# ESP32_Sheet.net
KiCad netlist of a schematic drawn in Altium Designer
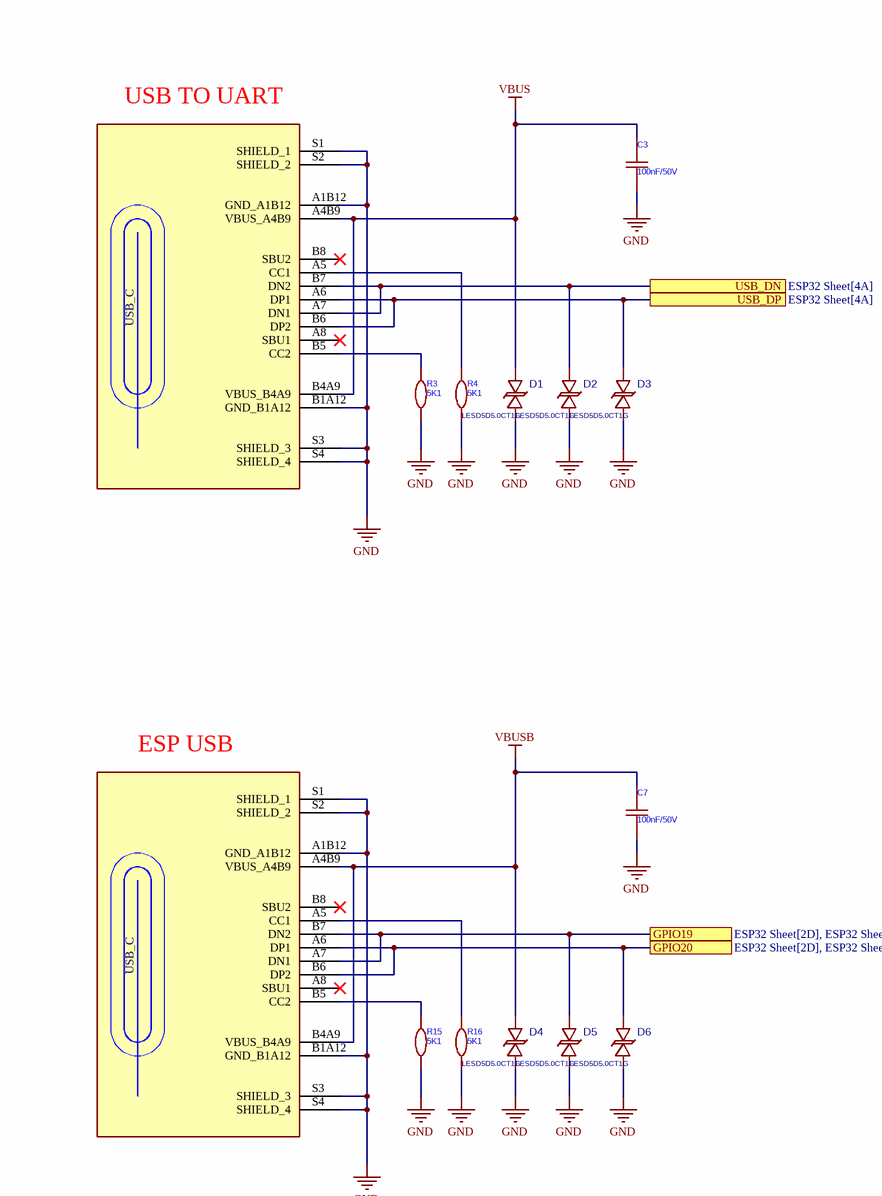
[diagram p0: ESP32 Sheet.SchDoc, top left]
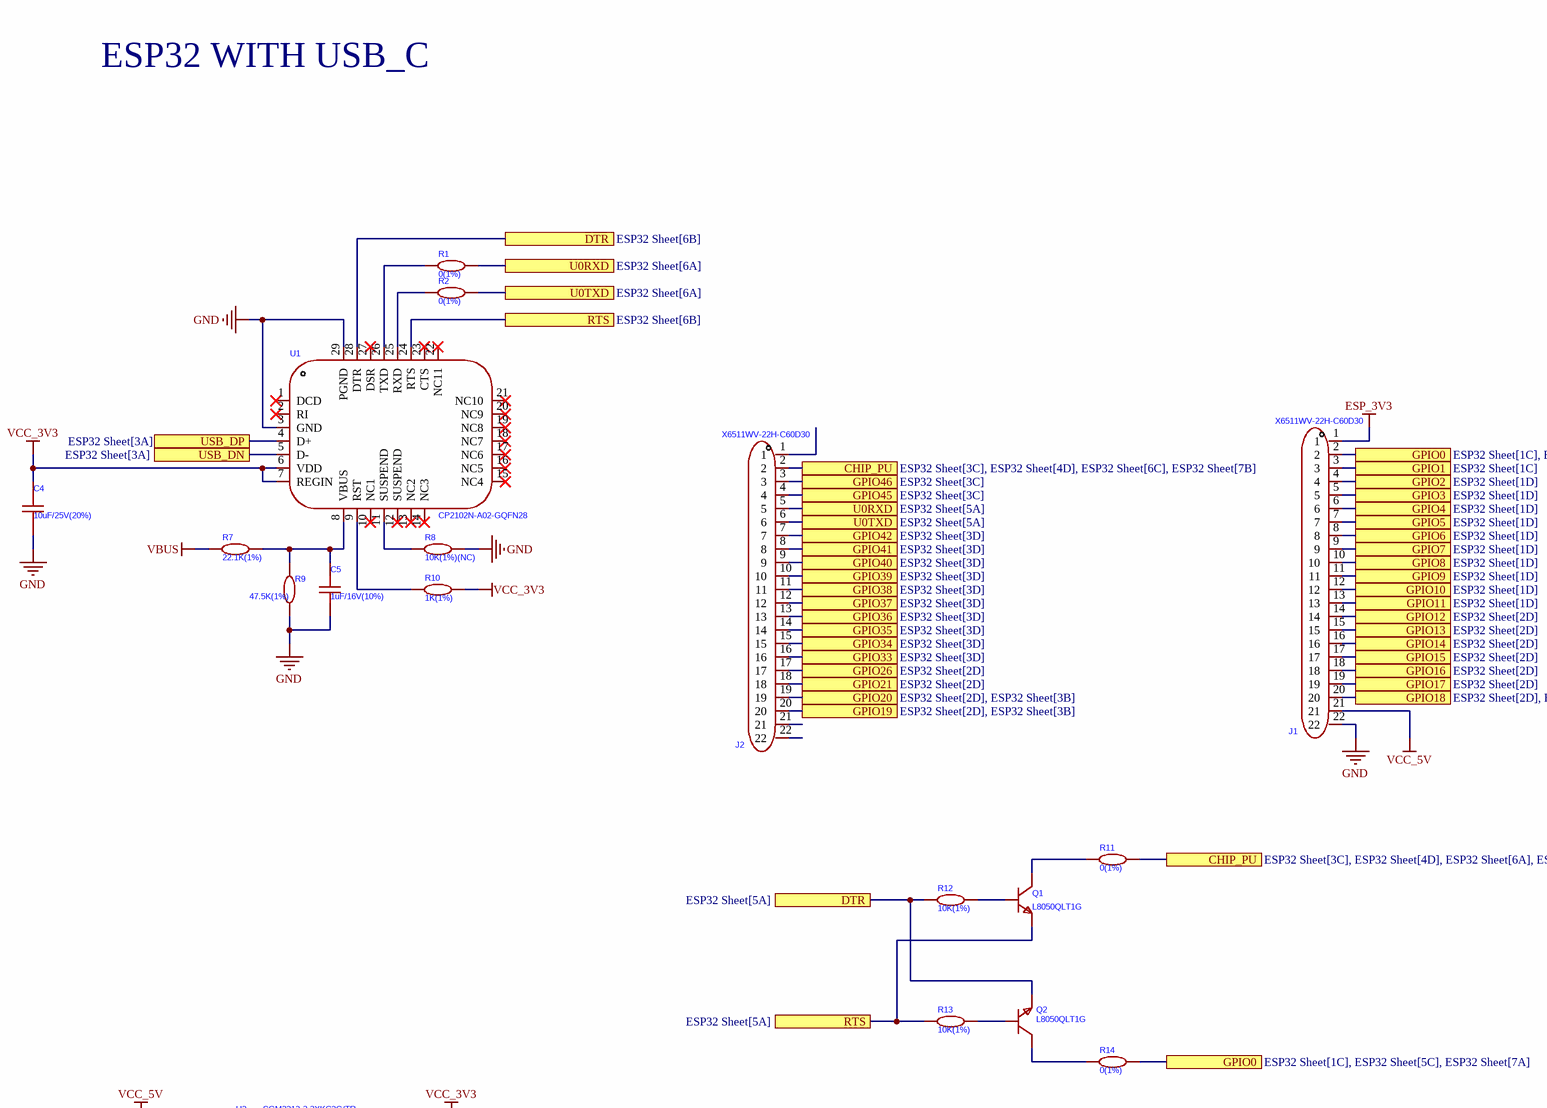
[diagram p1: ESP32 Sheet.SchDoc, top right]
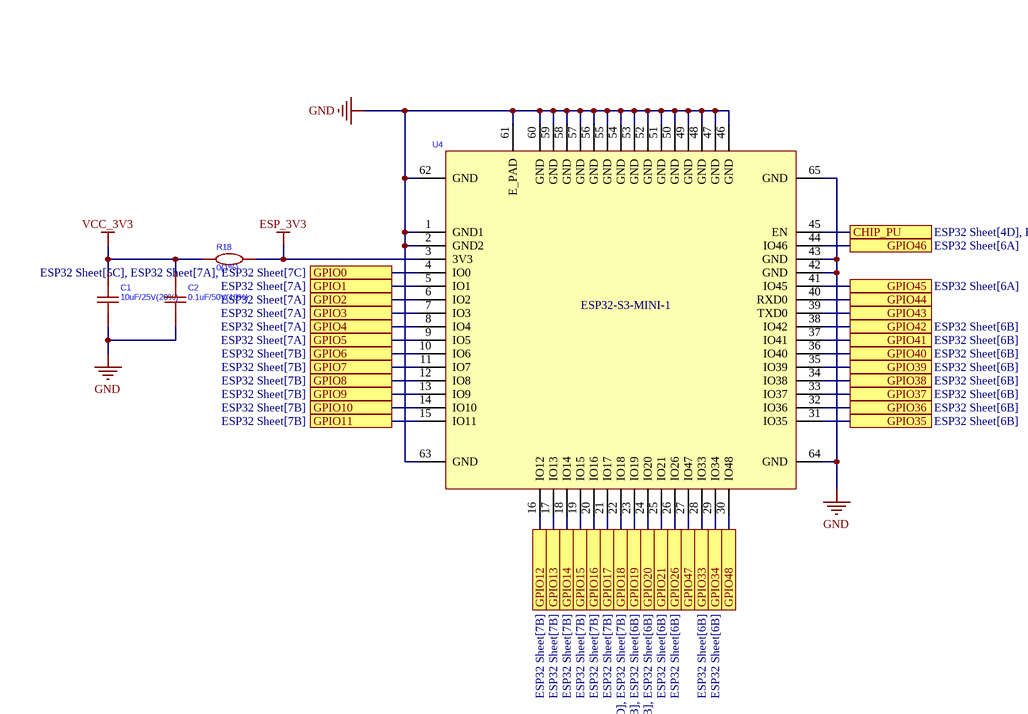
[diagram p2: ESP32 Sheet.SchDoc, bottom left]
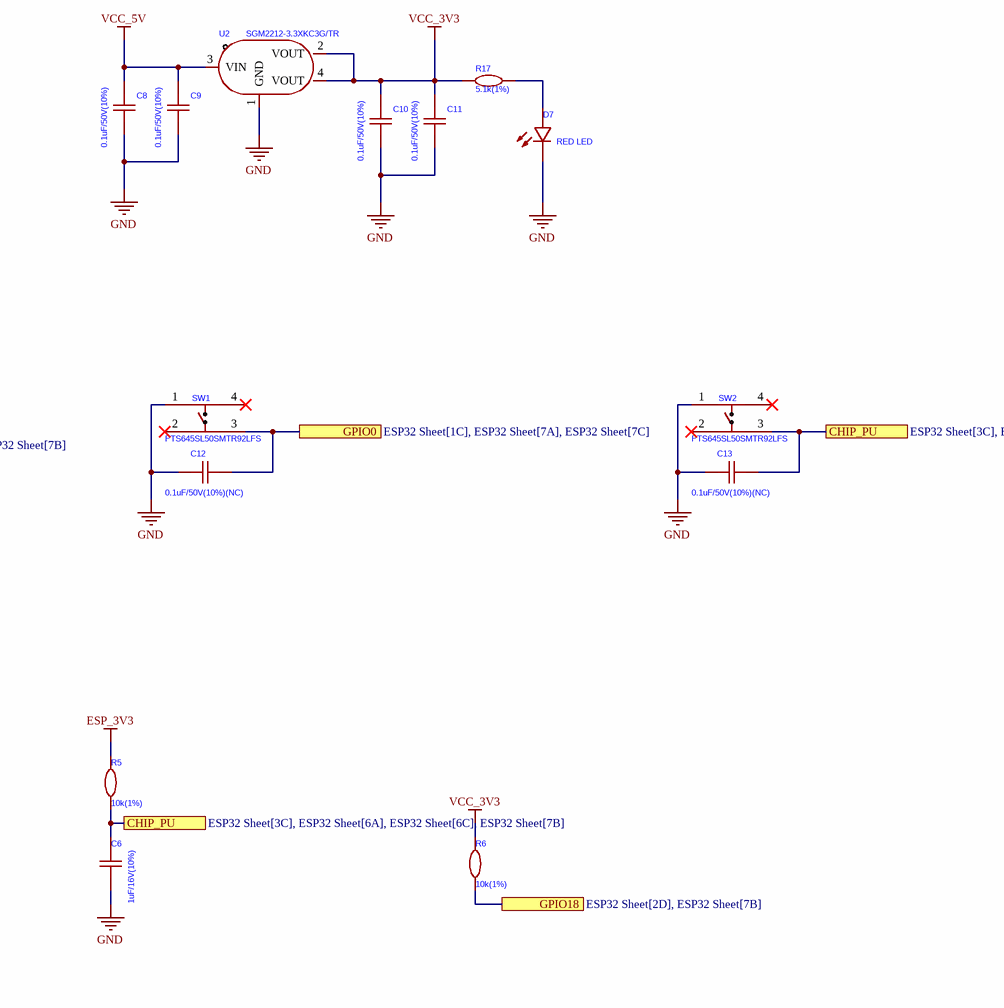
[diagram p3: ESP32 Sheet.SchDoc, bottom right]

(export (version "E")
  (design (tool "Eeschema 10.0.6"))
  (components
    (comp (ref "C1")
      (value "10uF/25V(20%)")
      (footprint "C0402")
      (fields
        (field (name "MANUFACTURER") "SAMSUNG(三星)")
        (field (name "MANUFACTURER PART") "CL05B104KB54PNC")
        (field (name "TOLERANCE") "±10%")
      )
      (libsource (lib "altium-import") (part "root_1_CL05B104KB54PNC_"))
    )
    (comp (ref "C2")
      (value "0.1uF/50V(10%)")
      (footprint "C0402")
      (fields
        (field (name "MANUFACTURER") "SAMSUNG(三星)")
        (field (name "MANUFACTURER PART") "CL05B104KB54PNC")
        (field (name "TOLERANCE") "±10%")
      )
      (libsource (lib "altium-import") (part "root_1_CL05B104KB54PNC_"))
    )
    (comp (ref "C3")
      (value "100nF/50V")
      (footprint "C0402")
      (fields
        (field (name "MANUFACTURER") "SAMSUNG(三星)")
        (field (name "MANUFACTURER PART") "CL05B104KB54PNC")
        (field (name "TOLERANCE") "±10%")
      )
      (libsource (lib "altium-import") (part "root_3_CL05B104KB54PNC_"))
    )
    (comp (ref "C4")
      (value "10uF/25V(20%)")
      (footprint "C0402")
      (fields
        (field (name "MANUFACTURER") "SAMSUNG(三星)")
        (field (name "MANUFACTURER PART") "CL05B104KB54PNC")
        (field (name "TOLERANCE") "±10%")
      )
      (libsource (lib "altium-import") (part "root_3_CL05B104KB54PNC_"))
    )
    (comp (ref "C5")
      (value "1uF/16V(10%)")
      (footprint "C0402")
      (fields
        (field (name "MANUFACTURER") "SAMSUNG(三星)")
        (field (name "MANUFACTURER PART") "CL05B104KB54PNC")
        (field (name "TOLERANCE") "±10%")
      )
      (libsource (lib "altium-import") (part "root_3_CL05B104KB54PNC_"))
    )
    (comp (ref "C6")
      (value "1uF/16V(10%)")
      (footprint "C0402")
      (fields
        (field (name "MANUFACTURER") "SAMSUNG(三星)")
        (field (name "MANUFACTURER PART") "CL05B104KB54PNC")
        (field (name "TOLERANCE") "±10%")
      )
      (libsource (lib "altium-import") (part "root_3_CL05B104KB54PNC_"))
    )
    (comp (ref "C7")
      (value "100nF/50V")
      (footprint "C0402")
      (fields
        (field (name "MANUFACTURER") "SAMSUNG(三星)")
        (field (name "MANUFACTURER PART") "CL05B104KB54PNC")
        (field (name "TOLERANCE") "±10%")
      )
      (libsource (lib "altium-import") (part "root_3_CL05B104KB54PNC_"))
    )
    (comp (ref "C8")
      (value "0.1uF/50V(10%)")
      (footprint "C0402")
      (fields
        (field (name "MANUFACTURER") "SAMSUNG(三星)")
        (field (name "MANUFACTURER PART") "CL05B104KB54PNC")
        (field (name "TOLERANCE") "±10%")
      )
      (libsource (lib "altium-import") (part "root_1_CL05B104KB54PNC_"))
    )
    (comp (ref "C9")
      (value "0.1uF/50V(10%)")
      (footprint "C0402")
      (fields
        (field (name "MANUFACTURER") "SAMSUNG(三星)")
        (field (name "MANUFACTURER PART") "CL05B104KB54PNC")
        (field (name "TOLERANCE") "±10%")
      )
      (libsource (lib "altium-import") (part "root_1_CL05B104KB54PNC_"))
    )
    (comp (ref "C10")
      (value "0.1uF/50V(10%)")
      (footprint "C0402")
      (fields
        (field (name "MANUFACTURER") "SAMSUNG(三星)")
        (field (name "MANUFACTURER PART") "CL05B104KB54PNC")
        (field (name "TOLERANCE") "±10%")
      )
      (libsource (lib "altium-import") (part "root_1_CL05B104KB54PNC_"))
    )
    (comp (ref "C11")
      (value "0.1uF/50V(10%)")
      (footprint "C0402")
      (fields
        (field (name "MANUFACTURER") "SAMSUNG(三星)")
        (field (name "MANUFACTURER PART") "CL05B104KB54PNC")
        (field (name "TOLERANCE") "±10%")
      )
      (libsource (lib "altium-import") (part "root_1_CL05B104KB54PNC_"))
    )
    (comp (ref "C12")
      (value "0.1uF/50V(10%)(NC)")
      (footprint "C0402")
      (fields
        (field (name "MANUFACTURER") "SAMSUNG(三星)")
        (field (name "MANUFACTURER PART") "CL05B104KB54PNC")
        (field (name "TOLERANCE") "±10%")
      )
      (libsource (lib "altium-import") (part "root_0_CL05B104KB54PNC_"))
    )
    (comp (ref "C13")
      (value "0.1uF/50V(10%)(NC)")
      (footprint "C0402")
      (fields
        (field (name "MANUFACTURER") "SAMSUNG(三星)")
        (field (name "MANUFACTURER PART") "CL05B104KB54PNC")
        (field (name "TOLERANCE") "±10%")
      )
      (libsource (lib "altium-import") (part "root_0_CL05B104KB54PNC_"))
    )
    (comp (ref "D1")
      (value "LESD5D5.0CT1G")
      (footprint "SOD-523_L1.2-W0.8-LS1.6-BI")
      (fields (field (name "MANUFACTURER") "UMW(友台半导体)") (field (name "CONTRIBUTOR") "lcsc"))
      (libsource (lib "altium-import") (part "root_1_LESD5D5.0CT1G_C5199850_"))
    )
    (comp (ref "D2")
      (value "LESD5D5.0CT1G")
      (footprint "SOD-523_L1.2-W0.8-LS1.6-BI")
      (fields (field (name "MANUFACTURER") "UMW(友台半导体)") (field (name "CONTRIBUTOR") "lcsc"))
      (libsource (lib "altium-import") (part "root_1_LESD5D5.0CT1G_C5199850_"))
    )
    (comp (ref "D3")
      (value "LESD5D5.0CT1G")
      (footprint "SOD-523_L1.2-W0.8-LS1.6-BI")
      (fields (field (name "MANUFACTURER") "UMW(友台半导体)") (field (name "CONTRIBUTOR") "lcsc"))
      (libsource (lib "altium-import") (part "root_1_LESD5D5.0CT1G_C5199850_"))
    )
    (comp (ref "D4")
      (value "LESD5D5.0CT1G")
      (footprint "SOD-523_L1.2-W0.8-LS1.6-BI")
      (fields (field (name "MANUFACTURER") "UMW(友台半导体)") (field (name "CONTRIBUTOR") "lcsc"))
      (libsource (lib "altium-import") (part "root_1_LESD5D5.0CT1G_C5199850_"))
    )
    (comp (ref "D5")
      (value "LESD5D5.0CT1G")
      (footprint "SOD-523_L1.2-W0.8-LS1.6-BI")
      (fields (field (name "MANUFACTURER") "UMW(友台半导体)") (field (name "CONTRIBUTOR") "lcsc"))
      (libsource (lib "altium-import") (part "root_1_LESD5D5.0CT1G_C5199850_"))
    )
    (comp (ref "D6")
      (value "LESD5D5.0CT1G")
      (footprint "SOD-523_L1.2-W0.8-LS1.6-BI")
      (fields (field (name "MANUFACTURER") "UMW(友台半导体)") (field (name "CONTRIBUTOR") "lcsc"))
      (libsource (lib "altium-import") (part "root_1_LESD5D5.0CT1G_C5199850_"))
    )
    (comp (ref "D7")
      (value "RED LED")
      (footprint "LED0402-R-RD")
      (fields
        (field (name "MANUFACTURER") "EVERLIGHT(亿光)")
        (field (name "MANUFACTURER PART") "16-213SDRC/S530-A3/TR8")
      )
      (libsource (lib "altium-import") (part "root_1_16-213SDRC/S530-A3/TR8_"))
    )
    (comp (ref "J1")
      (value "X6511WV-22H-C60D30")
      (footprint "HDR-TH_22P-P2.54-V-M")
      (fields (field (name "MANUFACTURER") "XKB Connection(中国星坤)"))
      (libsource (lib "altium-import") (part "root_0_mirrored_X6511WV-22H-C60D30_"))
    )
    (comp (ref "J2")
      (value "X6511WV-22H-C60D30")
      (footprint "HDR-TH_22P-P2.54-V-M")
      (fields (field (name "MANUFACTURER") "XKB Connection(中国星坤)"))
      (libsource (lib "altium-import") (part "root_0_mirrored_X6511WV-22H-C60D30_"))
    )
    (comp (ref "Q1")
      (value "L8050QLT1G")
      (footprint "SOT-23-3_L2.9-W1.3-P1.90-LS2.4-BR")
      (fields (field (name "MANUFACTURER") "LRC(乐山无线电)"))
      (libsource (lib "altium-import") (part "root_0_L8050QLT1G_"))
    )
    (comp (ref "Q2")
      (value "L8050QLT1G")
      (footprint "SOT-23-3_L2.9-W1.3-P1.90-LS2.4-BR")
      (fields (field (name "MANUFACTURER") "LRC(乐山无线电)"))
      (libsource (lib "altium-import") (part "root_2_mirrored_L8050QLT1G_"))
    )
    (comp (ref "R1")
      (value "0(1%)")
      (footprint "R0402")
      (fields
        (field (name "MANUFACTURER") "YAGEO(国巨)")
        (field (name "MANUFACTURER PART") "AC0402FR-0710KL")
        (field (name "TOLERANCE") "±1%")
      )
      (libsource (lib "altium-import") (part "root_2_AC0402FR-0710KL_"))
    )
    (comp (ref "R2")
      (value "0(1%)")
      (footprint "R0402")
      (fields
        (field (name "MANUFACTURER") "YAGEO(国巨)")
        (field (name "MANUFACTURER PART") "AC0402FR-0710KL")
        (field (name "TOLERANCE") "±1%")
      )
      (libsource (lib "altium-import") (part "root_2_AC0402FR-0710KL_"))
    )
    (comp (ref "R3")
      (value "5K1")
      (footprint "R0402")
      (fields
        (field (name "MANUFACTURER") "YAGEO(国巨)")
        (field (name "MANUFACTURER PART") "AC0402FR-0710KL")
        (field (name "TOLERANCE") "±1%")
      )
      (libsource (lib "altium-import") (part "root_1_AC0402FR-0710KL_"))
    )
    (comp (ref "R4")
      (value "5K1")
      (footprint "R0402")
      (fields
        (field (name "MANUFACTURER") "YAGEO(国巨)")
        (field (name "MANUFACTURER PART") "AC0402FR-0710KL")
        (field (name "TOLERANCE") "±1%")
      )
      (libsource (lib "altium-import") (part "root_1_AC0402FR-0710KL_"))
    )
    (comp (ref "R5")
      (value "10k(1%)")
      (footprint "R0402")
      (fields
        (field (name "MANUFACTURER") "YAGEO(国巨)")
        (field (name "MANUFACTURER PART") "AC0402FR-0710KL")
        (field (name "TOLERANCE") "±1%")
      )
      (libsource (lib "altium-import") (part "root_1_AC0402FR-0710KL_"))
    )
    (comp (ref "R6")
      (value "10k(1%)")
      (footprint "R0402")
      (fields
        (field (name "MANUFACTURER") "YAGEO(国巨)")
        (field (name "MANUFACTURER PART") "AC0402FR-0710KL")
        (field (name "TOLERANCE") "±1%")
      )
      (libsource (lib "altium-import") (part "root_1_AC0402FR-0710KL_"))
    )
    (comp (ref "R7")
      (value "22.1K(1%)")
      (footprint "R0402")
      (fields
        (field (name "MANUFACTURER") "YAGEO(国巨)")
        (field (name "MANUFACTURER PART") "AC0402FR-0710KL")
        (field (name "TOLERANCE") "±1%")
      )
      (libsource (lib "altium-import") (part "root_2_AC0402FR-0710KL_"))
    )
    (comp (ref "R8")
      (value "10K(1%)(NC)")
      (footprint "R0402")
      (fields
        (field (name "MANUFACTURER") "YAGEO(国巨)")
        (field (name "MANUFACTURER PART") "AC0402FR-0710KL")
        (field (name "TOLERANCE") "±1%")
      )
      (libsource (lib "altium-import") (part "root_2_AC0402FR-0710KL_"))
    )
    (comp (ref "R9")
      (value "47.5K(1%)")
      (footprint "R0402")
      (fields
        (field (name "MANUFACTURER") "YAGEO(国巨)")
        (field (name "MANUFACTURER PART") "AC0402FR-0710KL")
        (field (name "TOLERANCE") "±1%")
      )
      (libsource (lib "altium-import") (part "root_1_AC0402FR-0710KL_"))
    )
    (comp (ref "R10")
      (value "1K(1%)")
      (footprint "R0402")
      (fields
        (field (name "MANUFACTURER") "YAGEO(国巨)")
        (field (name "MANUFACTURER PART") "AC0402FR-0710KL")
        (field (name "TOLERANCE") "±1%")
      )
      (libsource (lib "altium-import") (part "root_2_AC0402FR-0710KL_"))
    )
    (comp (ref "R11")
      (value "0(1%)")
      (footprint "R0402")
      (fields
        (field (name "MANUFACTURER") "YAGEO(国巨)")
        (field (name "MANUFACTURER PART") "AC0402FR-0710KL")
        (field (name "TOLERANCE") "±1%")
      )
      (libsource (lib "altium-import") (part "root_2_AC0402FR-0710KL_"))
    )
    (comp (ref "R12")
      (value "10K(1%)")
      (footprint "R0402")
      (fields
        (field (name "MANUFACTURER") "YAGEO(国巨)")
        (field (name "MANUFACTURER PART") "AC0402FR-0710KL")
        (field (name "TOLERANCE") "±1%")
      )
      (libsource (lib "altium-import") (part "root_2_AC0402FR-0710KL_"))
    )
    (comp (ref "R13")
      (value "10K(1%)")
      (footprint "R0402")
      (fields
        (field (name "MANUFACTURER") "YAGEO(国巨)")
        (field (name "MANUFACTURER PART") "AC0402FR-0710KL")
        (field (name "TOLERANCE") "±1%")
      )
      (libsource (lib "altium-import") (part "root_2_AC0402FR-0710KL_"))
    )
    (comp (ref "R14")
      (value "0(1%)")
      (footprint "R0402")
      (fields
        (field (name "MANUFACTURER") "YAGEO(国巨)")
        (field (name "MANUFACTURER PART") "AC0402FR-0710KL")
        (field (name "TOLERANCE") "±1%")
      )
      (libsource (lib "altium-import") (part "root_2_AC0402FR-0710KL_"))
    )
    (comp (ref "R15")
      (value "5K1")
      (footprint "R0402")
      (fields
        (field (name "MANUFACTURER") "YAGEO(国巨)")
        (field (name "MANUFACTURER PART") "AC0402FR-0710KL")
        (field (name "TOLERANCE") "±1%")
      )
      (libsource (lib "altium-import") (part "root_1_AC0402FR-0710KL_"))
    )
    (comp (ref "R16")
      (value "5K1")
      (footprint "R0402")
      (fields
        (field (name "MANUFACTURER") "YAGEO(国巨)")
        (field (name "MANUFACTURER PART") "AC0402FR-0710KL")
        (field (name "TOLERANCE") "±1%")
      )
      (libsource (lib "altium-import") (part "root_1_AC0402FR-0710KL_"))
    )
    (comp (ref "R17")
      (value "5.1k(1%)")
      (footprint "R0402")
      (fields
        (field (name "MANUFACTURER") "YAGEO(国巨)")
        (field (name "MANUFACTURER PART") "AC0402FR-0710KL")
        (field (name "TOLERANCE") "±1%")
      )
      (libsource (lib "altium-import") (part "root_2_AC0402FR-0710KL_"))
    )
    (comp (ref "R18")
      (value "0(1%)")
      (footprint "R0402")
      (fields
        (field (name "MANUFACTURER") "YAGEO(国巨)")
        (field (name "MANUFACTURER PART") "AC0402FR-0710KL")
        (field (name "TOLERANCE") "±1%")
      )
      (libsource (lib "altium-import") (part "root_2_AC0402FR-0710KL_"))
    )
    (comp (ref "SW1")
      (value "PTS645SL50SMTR92LFS")
      (footprint "KEY-SMD_4P-L6.0-W6.0-P4.50-LS9.0")
      (fields (field (name "MANUFACTURER") "C&K"))
      (libsource (lib "Schlib1") (part "PTS645SL50SMTR92LFS"))
    )
    (comp (ref "SW2")
      (value "PTS645SL50SMTR92LFS")
      (footprint "KEY-SMD_4P-L6.0-W6.0-P4.50-LS9.0")
      (fields (field (name "MANUFACTURER") "C&K"))
      (libsource (lib "Schlib1") (part "PTS645SL50SMTR92LFS"))
    )
    (comp (ref "U1")
      (value "CP2102N-A02-GQFN28")
      (footprint "QFN-28_L5.0-W5.0-P0.50-TL-EP3.3")
      (fields (field (name "MANUFACTURER") "SKYWORKS/SILICON LABS(芯科)"))
      (libsource (lib "Schlib1") (part "CP2102N-A02-GQFN28"))
    )
    (comp (ref "U2")
      (value "SGM2212-3.3XKC3G/TR")
      (footprint "SOT-223-3_L6.5-W3.4-P2.30-LS7.0-BR")
      (fields (field (name "MANUFACTURER") "SGMICRO(圣邦微)"))
      (libsource (lib "Schlib1") (part "SGM2212-3.3XKC3G/TR_C3294699"))
    )
    (comp (ref "U4")
      (value "2.4GHz")
      (footprint "BULETM-SMD_ESP32-S3-MINI-1-N8")
      (fields
        (field (name "MANUFACTURER") "ESPRESSIF(乐鑫)")
        (field (name "MANUFACTURER PART") "ESP32-S3-MINI-1-N8")
      )
      (libsource (lib "Schlib1") (part "ESP32-S3-MINI-1-N8"))
    )
    (comp (ref "USB1")
      (value "2171790001")
      (footprint "USB-C-SMD_2171790001")
      (fields (field (name "MANUFACTURER") "MOLEX"))
      (libsource (lib "Schlib1") (part "2171790001"))
    )
    (comp (ref "USB2")
      (value "2171790001")
      (footprint "USB-C-SMD_2171790001")
      (fields (field (name "MANUFACTURER") "MOLEX"))
      (libsource (lib "Schlib1") (part "2171790001"))
    )
  )
  (nets
    (net (code "1") (name "/CHIP_PU") (class "Default")
      (node (ref "C13") (pin "2") (pinfunction "2_2") (pintype "passive"))
      (node (ref "C6") (pin "1") (pinfunction "1_1") (pintype "passive"))
      (node (ref "J2") (pin "2") (pinfunction "2_2") (pintype "passive"))
      (node (ref "R11") (pin "1") (pinfunction "1_1") (pintype "passive"))
      (node (ref "R5") (pin "1") (pinfunction "1_1") (pintype "passive"))
      (node (ref "SW2") (pin "3") (pinfunction "3_3") (pintype "passive"))
      (node (ref "U4") (pin "45") (pinfunction "EN_45") (pintype "passive"))
    )
    (net (code "2") (name "/DTR") (class "Default")
      (node (ref "Q2") (pin "2") (pinfunction "E_2") (pintype "passive"))
      (node (ref "R12") (pin "2") (pinfunction "2_2") (pintype "passive"))
      (node (ref "U1") (pin "28") (pinfunction "DTR_28") (pintype "passive"))
    )
    (net (code "3") (name "/GPIO0") (class "Default")
      (node (ref "C12") (pin "2") (pinfunction "2_2") (pintype "passive"))
      (node (ref "J1") (pin "2") (pinfunction "2_2") (pintype "passive"))
      (node (ref "R14") (pin "1") (pinfunction "1_1") (pintype "passive"))
      (node (ref "SW1") (pin "3") (pinfunction "3_3") (pintype "passive"))
      (node (ref "U4") (pin "4") (pinfunction "IO0_4") (pintype "passive"))
    )
    (net (code "4") (name "/GPIO1") (class "Default")
      (node (ref "J1") (pin "3") (pinfunction "3_3") (pintype "passive"))
      (node (ref "U4") (pin "5") (pinfunction "IO1_5") (pintype "passive"))
    )
    (net (code "5") (name "/GPIO2") (class "Default")
      (node (ref "J1") (pin "4") (pinfunction "4_4") (pintype "passive"))
      (node (ref "U4") (pin "6") (pinfunction "IO2_6") (pintype "passive"))
    )
    (net (code "6") (name "/GPIO3") (class "Default")
      (node (ref "J1") (pin "5") (pinfunction "5_5") (pintype "passive"))
      (node (ref "U4") (pin "7") (pinfunction "IO3_7") (pintype "passive"))
    )
    (net (code "7") (name "/GPIO4") (class "Default")
      (node (ref "J1") (pin "6") (pinfunction "6_6") (pintype "passive"))
      (node (ref "U4") (pin "8") (pinfunction "IO4_8") (pintype "passive"))
    )
    (net (code "8") (name "/GPIO5") (class "Default")
      (node (ref "J1") (pin "7") (pinfunction "7_7") (pintype "passive"))
      (node (ref "U4") (pin "9") (pinfunction "IO5_9") (pintype "passive"))
    )
    (net (code "9") (name "/GPIO6") (class "Default")
      (node (ref "J1") (pin "8") (pinfunction "8_8") (pintype "passive"))
      (node (ref "U4") (pin "10") (pinfunction "IO6_10") (pintype "passive"))
    )
    (net (code "10") (name "/GPIO7") (class "Default")
      (node (ref "J1") (pin "9") (pinfunction "9_9") (pintype "passive"))
      (node (ref "U4") (pin "11") (pinfunction "IO7_11") (pintype "passive"))
    )
    (net (code "11") (name "/GPIO8") (class "Default")
      (node (ref "J1") (pin "10") (pinfunction "10_10") (pintype "passive"))
      (node (ref "U4") (pin "12") (pinfunction "IO8_12") (pintype "passive"))
    )
    (net (code "12") (name "/GPIO9") (class "Default")
      (node (ref "J1") (pin "11") (pinfunction "11_11") (pintype "passive"))
      (node (ref "U4") (pin "13") (pinfunction "IO9_13") (pintype "passive"))
    )
    (net (code "13") (name "/GPIO10") (class "Default")
      (node (ref "J1") (pin "12") (pinfunction "12_12") (pintype "passive"))
      (node (ref "U4") (pin "14") (pinfunction "IO10_14") (pintype "passive"))
    )
    (net (code "14") (name "/GPIO11") (class "Default")
      (node (ref "J1") (pin "13") (pinfunction "13_13") (pintype "passive"))
      (node (ref "U4") (pin "15") (pinfunction "IO11_15") (pintype "passive"))
    )
    (net (code "15") (name "/GPIO12") (class "Default")
      (node (ref "J1") (pin "14") (pinfunction "14_14") (pintype "passive"))
      (node (ref "U4") (pin "16") (pinfunction "IO12_16") (pintype "passive"))
    )
    (net (code "16") (name "/GPIO13") (class "Default")
      (node (ref "J1") (pin "15") (pinfunction "15_15") (pintype "passive"))
      (node (ref "U4") (pin "17") (pinfunction "IO13_17") (pintype "passive"))
    )
    (net (code "17") (name "/GPIO14") (class "Default")
      (node (ref "J1") (pin "16") (pinfunction "16_16") (pintype "passive"))
      (node (ref "U4") (pin "18") (pinfunction "IO14_18") (pintype "passive"))
    )
    (net (code "18") (name "/GPIO15") (class "Default")
      (node (ref "J1") (pin "17") (pinfunction "17_17") (pintype "passive"))
      (node (ref "U4") (pin "19") (pinfunction "IO15_19") (pintype "passive"))
    )
    (net (code "19") (name "/GPIO16") (class "Default")
      (node (ref "J1") (pin "18") (pinfunction "18_18") (pintype "passive"))
      (node (ref "U4") (pin "20") (pinfunction "IO16_20") (pintype "passive"))
    )
    (net (code "20") (name "/GPIO17") (class "Default")
      (node (ref "J1") (pin "19") (pinfunction "19_19") (pintype "passive"))
      (node (ref "U4") (pin "21") (pinfunction "IO17_21") (pintype "passive"))
    )
    (net (code "21") (name "/GPIO18") (class "Default")
      (node (ref "J1") (pin "20") (pinfunction "20_20") (pintype "passive"))
      (node (ref "R6") (pin "1") (pinfunction "1_1") (pintype "passive"))
      (node (ref "U4") (pin "22") (pinfunction "IO18_22") (pintype "passive"))
    )
    (net (code "22") (name "/GPIO19") (class "Default")
      (node (ref "D5") (pin "2") (pinfunction "2_2") (pintype "passive"))
      (node (ref "J2") (pin "20") (pinfunction "20_20") (pintype "passive"))
      (node (ref "U4") (pin "23") (pinfunction "IO19_23") (pintype "passive"))
      (node (ref "USB2") (pin "A7") (pinfunction "DN1_A7") (pintype "passive"))
      (node (ref "USB2") (pin "B7") (pinfunction "DN2_B7") (pintype "passive"))
    )
    (net (code "23") (name "/GPIO20") (class "Default")
      (node (ref "D6") (pin "2") (pinfunction "2_2") (pintype "passive"))
      (node (ref "J2") (pin "19") (pinfunction "19_19") (pintype "passive"))
      (node (ref "U4") (pin "24") (pinfunction "IO20_24") (pintype "passive"))
      (node (ref "USB2") (pin "A6") (pinfunction "DP1_A6") (pintype "passive"))
      (node (ref "USB2") (pin "B6") (pinfunction "DP2_B6") (pintype "passive"))
    )
    (net (code "24") (name "/GPIO21") (class "Default")
      (node (ref "J2") (pin "18") (pinfunction "18_18") (pintype "passive"))
      (node (ref "U4") (pin "25") (pinfunction "IO21_25") (pintype "passive"))
    )
    (net (code "25") (name "/GPIO26") (class "Default")
      (node (ref "J2") (pin "17") (pinfunction "17_17") (pintype "passive"))
      (node (ref "U4") (pin "26") (pinfunction "IO26_26") (pintype "passive"))
    )
    (net (code "26") (name "/GPIO33") (class "Default")
      (node (ref "J2") (pin "16") (pinfunction "16_16") (pintype "passive"))
      (node (ref "U4") (pin "28") (pinfunction "IO33_28") (pintype "passive"))
    )
    (net (code "27") (name "/GPIO34") (class "Default")
      (node (ref "J2") (pin "15") (pinfunction "15_15") (pintype "passive"))
      (node (ref "U4") (pin "29") (pinfunction "IO34_29") (pintype "passive"))
    )
    (net (code "28") (name "/GPIO35") (class "Default")
      (node (ref "J2") (pin "14") (pinfunction "14_14") (pintype "passive"))
      (node (ref "U4") (pin "31") (pinfunction "IO35_31") (pintype "passive"))
    )
    (net (code "29") (name "/GPIO36") (class "Default")
      (node (ref "J2") (pin "13") (pinfunction "13_13") (pintype "passive"))
      (node (ref "U4") (pin "32") (pinfunction "IO36_32") (pintype "passive"))
    )
    (net (code "30") (name "/GPIO37") (class "Default")
      (node (ref "J2") (pin "12") (pinfunction "12_12") (pintype "passive"))
      (node (ref "U4") (pin "33") (pinfunction "IO37_33") (pintype "passive"))
    )
    (net (code "31") (name "/GPIO38") (class "Default")
      (node (ref "J2") (pin "11") (pinfunction "11_11") (pintype "passive"))
      (node (ref "U4") (pin "34") (pinfunction "IO38_34") (pintype "passive"))
    )
    (net (code "32") (name "/GPIO39") (class "Default")
      (node (ref "J2") (pin "10") (pinfunction "10_10") (pintype "passive"))
      (node (ref "U4") (pin "35") (pinfunction "IO39_35") (pintype "passive"))
    )
    (net (code "33") (name "/GPIO40") (class "Default")
      (node (ref "J2") (pin "9") (pinfunction "9_9") (pintype "passive"))
      (node (ref "U4") (pin "36") (pinfunction "IO40_36") (pintype "passive"))
    )
    (net (code "34") (name "/GPIO41") (class "Default")
      (node (ref "J2") (pin "8") (pinfunction "8_8") (pintype "passive"))
      (node (ref "U4") (pin "37") (pinfunction "IO41_37") (pintype "passive"))
    )
    (net (code "35") (name "/GPIO42") (class "Default")
      (node (ref "J2") (pin "7") (pinfunction "7_7") (pintype "passive"))
      (node (ref "U4") (pin "38") (pinfunction "IO42_38") (pintype "passive"))
    )
    (net (code "36") (name "/GPIO43") (class "Default")
      (node (ref "U4") (pin "39") (pinfunction "TXD0_39") (pintype "passive"))
    )
    (net (code "37") (name "/GPIO44") (class "Default")
      (node (ref "U4") (pin "40") (pinfunction "RXD0_40") (pintype "passive"))
    )
    (net (code "38") (name "/GPIO45") (class "Default")
      (node (ref "J2") (pin "4") (pinfunction "4_4") (pintype "passive"))
      (node (ref "U4") (pin "41") (pinfunction "IO45_41") (pintype "passive"))
    )
    (net (code "39") (name "/GPIO46") (class "Default")
      (node (ref "J2") (pin "3") (pinfunction "3_3") (pintype "passive"))
      (node (ref "U4") (pin "44") (pinfunction "IO46_44") (pintype "passive"))
    )
    (net (code "40") (name "/GPIO47") (class "Default")
      (node (ref "U4") (pin "27") (pinfunction "IO47_27") (pintype "passive"))
    )
    (net (code "41") (name "/GPIO48") (class "Default")
      (node (ref "U4") (pin "30") (pinfunction "IO48_30") (pintype "passive"))
    )
    (net (code "42") (name "/RTS") (class "Default")
      (node (ref "Q1") (pin "2") (pinfunction "E_2") (pintype "passive"))
      (node (ref "R13") (pin "2") (pinfunction "2_2") (pintype "passive"))
      (node (ref "U1") (pin "24") (pinfunction "RTS_24") (pintype "passive"))
    )
    (net (code "43") (name "/U0RXD") (class "Default")
      (node (ref "J2") (pin "5") (pinfunction "5_5") (pintype "passive"))
      (node (ref "R1") (pin "1") (pinfunction "1_1") (pintype "passive"))
    )
    (net (code "44") (name "/U0TXD") (class "Default")
      (node (ref "J2") (pin "6") (pinfunction "6_6") (pintype "passive"))
      (node (ref "R2") (pin "1") (pinfunction "1_1") (pintype "passive"))
    )
    (net (code "45") (name "/USB_DN") (class "Default")
      (node (ref "D2") (pin "2") (pinfunction "2_2") (pintype "passive"))
      (node (ref "U1") (pin "5") (pinfunction "D-_5") (pintype "passive"))
      (node (ref "USB1") (pin "A7") (pinfunction "DN1_A7") (pintype "passive"))
      (node (ref "USB1") (pin "B7") (pinfunction "DN2_B7") (pintype "passive"))
    )
    (net (code "46") (name "/USB_DP") (class "Default")
      (node (ref "D3") (pin "2") (pinfunction "2_2") (pintype "passive"))
      (node (ref "U1") (pin "4") (pinfunction "D+_4") (pintype "passive"))
      (node (ref "USB1") (pin "A6") (pinfunction "DP1_A6") (pintype "passive"))
      (node (ref "USB1") (pin "B6") (pinfunction "DP2_B6") (pintype "passive"))
    )
    (net (code "47") (name "ESP_3V3") (class "Default")
      (node (ref "J1") (pin "1") (pinfunction "1_1") (pintype "passive"))
      (node (ref "R18") (pin "1") (pinfunction "1_1") (pintype "passive"))
      (node (ref "R5") (pin "2") (pinfunction "2_2") (pintype "passive"))
      (node (ref "U4") (pin "3") (pinfunction "3V3_3") (pintype "passive"))
    )
    (net (code "48") (name "GND") (class "Default")
      (node (ref "C1") (pin "1") (pinfunction "1_1") (pintype "passive"))
      (node (ref "C10") (pin "1") (pinfunction "1_1") (pintype "passive"))
      (node (ref "C11") (pin "1") (pinfunction "1_1") (pintype "passive"))
      (node (ref "C12") (pin "1") (pinfunction "1_1") (pintype "passive"))
      (node (ref "C13") (pin "1") (pinfunction "1_1") (pintype "passive"))
      (node (ref "C2") (pin "1") (pinfunction "1_1") (pintype "passive"))
      (node (ref "C3") (pin "2") (pinfunction "2_2") (pintype "passive"))
      (node (ref "C4") (pin "2") (pinfunction "2_2") (pintype "passive"))
      (node (ref "C5") (pin "2") (pinfunction "2_2") (pintype "passive"))
      (node (ref "C6") (pin "2") (pinfunction "2_2") (pintype "passive"))
      (node (ref "C7") (pin "2") (pinfunction "2_2") (pintype "passive"))
      (node (ref "C8") (pin "1") (pinfunction "1_1") (pintype "passive"))
      (node (ref "C9") (pin "1") (pinfunction "1_1") (pintype "passive"))
      (node (ref "D1") (pin "1") (pinfunction "1_1") (pintype "passive"))
      (node (ref "D2") (pin "1") (pinfunction "1_1") (pintype "passive"))
      (node (ref "D3") (pin "1") (pinfunction "1_1") (pintype "passive"))
      (node (ref "D4") (pin "1") (pinfunction "1_1") (pintype "passive"))
      (node (ref "D5") (pin "1") (pinfunction "1_1") (pintype "passive"))
      (node (ref "D6") (pin "1") (pinfunction "1_1") (pintype "passive"))
      (node (ref "D7") (pin "2") (pinfunction "-_2") (pintype "passive"))
      (node (ref "J1") (pin "22") (pinfunction "22_22") (pintype "passive"))
      (node (ref "R15") (pin "1") (pinfunction "1_1") (pintype "passive"))
      (node (ref "R16") (pin "1") (pinfunction "1_1") (pintype "passive"))
      (node (ref "R3") (pin "1") (pinfunction "1_1") (pintype "passive"))
      (node (ref "R4") (pin "1") (pinfunction "1_1") (pintype "passive"))
      (node (ref "R8") (pin "1") (pinfunction "1_1") (pintype "passive"))
      (node (ref "R9") (pin "1") (pinfunction "1_1") (pintype "passive"))
      (node (ref "SW1") (pin "1") (pinfunction "1_1") (pintype "passive"))
      (node (ref "SW2") (pin "1") (pinfunction "1_1") (pintype "passive"))
      (node (ref "U1") (pin "29") (pinfunction "PGND_29") (pintype "passive"))
      (node (ref "U1") (pin "3") (pinfunction "GND_3") (pintype "passive"))
      (node (ref "U2") (pin "1") (pinfunction "GND_1") (pintype "passive"))
      (node (ref "U4") (pin "1") (pinfunction "GND1_1") (pintype "passive"))
      (node (ref "U4") (pin "2") (pinfunction "GND2_2") (pintype "passive"))
      (node (ref "U4") (pin "42") (pinfunction "GND_42") (pintype "passive"))
      (node (ref "U4") (pin "43") (pinfunction "GND_43") (pintype "passive"))
      (node (ref "U4") (pin "46") (pinfunction "GND_46") (pintype "passive"))
      (node (ref "U4") (pin "47") (pinfunction "GND_47") (pintype "passive"))
      (node (ref "U4") (pin "48") (pinfunction "GND_48") (pintype "passive"))
      (node (ref "U4") (pin "49") (pinfunction "GND_49") (pintype "passive"))
      (node (ref "U4") (pin "50") (pinfunction "GND_50") (pintype "passive"))
      (node (ref "U4") (pin "51") (pinfunction "GND_51") (pintype "passive"))
      (node (ref "U4") (pin "52") (pinfunction "GND_52") (pintype "passive"))
      (node (ref "U4") (pin "53") (pinfunction "GND_53") (pintype "passive"))
      (node (ref "U4") (pin "54") (pinfunction "GND_54") (pintype "passive"))
      (node (ref "U4") (pin "55") (pinfunction "GND_55") (pintype "passive"))
      (node (ref "U4") (pin "56") (pinfunction "GND_56") (pintype "passive"))
      (node (ref "U4") (pin "57") (pinfunction "GND_57") (pintype "passive"))
      (node (ref "U4") (pin "58") (pinfunction "GND_58") (pintype "passive"))
      (node (ref "U4") (pin "59") (pinfunction "GND_59") (pintype "passive"))
      (node (ref "U4") (pin "60") (pinfunction "GND_60") (pintype "passive"))
      (node (ref "U4") (pin "61") (pinfunction "E_PAD_61") (pintype "passive"))
      (node (ref "U4") (pin "62") (pinfunction "GND_62") (pintype "passive"))
      (node (ref "U4") (pin "63") (pinfunction "GND_63") (pintype "passive"))
      (node (ref "U4") (pin "64") (pinfunction "GND_64") (pintype "passive"))
      (node (ref "U4") (pin "65") (pinfunction "GND_65") (pintype "passive"))
      (node (ref "USB1") (pin "A1B12") (pinfunction "GND_A1B12_A1B12") (pintype "passive"))
      (node (ref "USB1") (pin "B1A12") (pinfunction "GND_B1A12_B1A12") (pintype "passive"))
      (node (ref "USB1") (pin "S1") (pinfunction "SHIELD_1_S1") (pintype "passive"))
      (node (ref "USB1") (pin "S2") (pinfunction "SHIELD_2_S2") (pintype "passive"))
      (node (ref "USB1") (pin "S3") (pinfunction "SHIELD_3_S3") (pintype "passive"))
      (node (ref "USB1") (pin "S4") (pinfunction "SHIELD_4_S4") (pintype "passive"))
      (node (ref "USB2") (pin "A1B12") (pinfunction "GND_A1B12_A1B12") (pintype "passive"))
      (node (ref "USB2") (pin "B1A12") (pinfunction "GND_B1A12_B1A12") (pintype "passive"))
      (node (ref "USB2") (pin "S1") (pinfunction "SHIELD_1_S1") (pintype "passive"))
      (node (ref "USB2") (pin "S2") (pinfunction "SHIELD_2_S2") (pintype "passive"))
      (node (ref "USB2") (pin "S3") (pinfunction "SHIELD_3_S3") (pintype "passive"))
      (node (ref "USB2") (pin "S4") (pinfunction "SHIELD_4_S4") (pintype "passive"))
    )
    (net (code "49") (name "Net-(D7-+)") (class "Default")
      (node (ref "D7") (pin "1") (pinfunction "+_1") (pintype "passive"))
      (node (ref "R17") (pin "1") (pinfunction "1_1") (pintype "passive"))
    )
    (net (code "50") (name "Net-(Q1-B)") (class "Default")
      (node (ref "Q1") (pin "1") (pinfunction "B_1") (pintype "passive"))
      (node (ref "R12") (pin "1") (pinfunction "1_1") (pintype "passive"))
    )
    (net (code "51") (name "Net-(Q1-C)") (class "Default")
      (node (ref "Q1") (pin "3") (pinfunction "C_3") (pintype "passive"))
      (node (ref "R11") (pin "2") (pinfunction "2_2") (pintype "passive"))
    )
    (net (code "52") (name "Net-(Q2-B)") (class "Default")
      (node (ref "Q2") (pin "1") (pinfunction "B_1") (pintype "passive"))
      (node (ref "R13") (pin "1") (pinfunction "1_1") (pintype "passive"))
    )
    (net (code "53") (name "Net-(Q2-C)") (class "Default")
      (node (ref "Q2") (pin "3") (pinfunction "C_3") (pintype "passive"))
      (node (ref "R14") (pin "2") (pinfunction "2_2") (pintype "passive"))
    )
    (net (code "54") (name "Net-(R8-Pad2)") (class "Default")
      (node (ref "R8") (pin "2") (pinfunction "2_2") (pintype "passive"))
      (node (ref "U1") (pin "11") (pinfunction "SUSPEND_11") (pintype "passive"))
    )
    (net (code "55") (name "Net-(U1-RST)") (class "Default")
      (node (ref "R10") (pin "2") (pinfunction "2_2") (pintype "passive"))
      (node (ref "U1") (pin "9") (pinfunction "RST_9") (pintype "passive"))
    )
    (net (code "56") (name "Net-(U1-RXD)") (class "Default")
      (node (ref "R2") (pin "2") (pinfunction "2_2") (pintype "passive"))
      (node (ref "U1") (pin "25") (pinfunction "RXD_25") (pintype "passive"))
    )
    (net (code "57") (name "Net-(U1-TXD)") (class "Default")
      (node (ref "R1") (pin "2") (pinfunction "2_2") (pintype "passive"))
      (node (ref "U1") (pin "26") (pinfunction "TXD_26") (pintype "passive"))
    )
    (net (code "58") (name "Net-(U1-VBUS)") (class "Default")
      (node (ref "C5") (pin "1") (pinfunction "1_1") (pintype "passive"))
      (node (ref "R7") (pin "1") (pinfunction "1_1") (pintype "passive"))
      (node (ref "R9") (pin "2") (pinfunction "2_2") (pintype "passive"))
      (node (ref "U1") (pin "8") (pinfunction "VBUS_8") (pintype "passive"))
    )
    (net (code "59") (name "Net-(USB1-CC1)") (class "Default")
      (node (ref "R4") (pin "2") (pinfunction "2_2") (pintype "passive"))
      (node (ref "USB1") (pin "A5") (pinfunction "CC1_A5") (pintype "passive"))
    )
    (net (code "60") (name "Net-(USB1-CC2)") (class "Default")
      (node (ref "R3") (pin "2") (pinfunction "2_2") (pintype "passive"))
      (node (ref "USB1") (pin "B5") (pinfunction "CC2_B5") (pintype "passive"))
    )
    (net (code "61") (name "Net-(USB2-CC1)") (class "Default")
      (node (ref "R16") (pin "2") (pinfunction "2_2") (pintype "passive"))
      (node (ref "USB2") (pin "A5") (pinfunction "CC1_A5") (pintype "passive"))
    )
    (net (code "62") (name "Net-(USB2-CC2)") (class "Default")
      (node (ref "R15") (pin "2") (pinfunction "2_2") (pintype "passive"))
      (node (ref "USB2") (pin "B5") (pinfunction "CC2_B5") (pintype "passive"))
    )
    (net (code "63") (name "VBUS") (class "Default")
      (node (ref "C3") (pin "1") (pinfunction "1_1") (pintype "passive"))
      (node (ref "D1") (pin "2") (pinfunction "2_2") (pintype "passive"))
      (node (ref "R7") (pin "2") (pinfunction "2_2") (pintype "passive"))
      (node (ref "USB1") (pin "A4B9") (pinfunction "VBUS_A4B9_A4B9") (pintype "passive"))
      (node (ref "USB1") (pin "B4A9") (pinfunction "VBUS_B4A9_B4A9") (pintype "passive"))
    )
    (net (code "64") (name "VBUSB") (class "Default")
      (node (ref "C7") (pin "1") (pinfunction "1_1") (pintype "passive"))
      (node (ref "D4") (pin "2") (pinfunction "2_2") (pintype "passive"))
      (node (ref "USB2") (pin "A4B9") (pinfunction "VBUS_A4B9_A4B9") (pintype "passive"))
      (node (ref "USB2") (pin "B4A9") (pinfunction "VBUS_B4A9_B4A9") (pintype "passive"))
    )
    (net (code "65") (name "VCC_3V3") (class "Default")
      (node (ref "C1") (pin "2") (pinfunction "2_2") (pintype "passive"))
      (node (ref "C10") (pin "2") (pinfunction "2_2") (pintype "passive"))
      (node (ref "C11") (pin "2") (pinfunction "2_2") (pintype "passive"))
      (node (ref "C2") (pin "2") (pinfunction "2_2") (pintype "passive"))
      (node (ref "C4") (pin "1") (pinfunction "1_1") (pintype "passive"))
      (node (ref "R10") (pin "1") (pinfunction "1_1") (pintype "passive"))
      (node (ref "R17") (pin "2") (pinfunction "2_2") (pintype "passive"))
      (node (ref "R18") (pin "2") (pinfunction "2_2") (pintype "passive"))
      (node (ref "R6") (pin "2") (pinfunction "2_2") (pintype "passive"))
      (node (ref "U1") (pin "6") (pinfunction "VDD_6") (pintype "passive"))
      (node (ref "U1") (pin "7") (pinfunction "REGIN_7") (pintype "passive"))
      (node (ref "U2") (pin "2") (pinfunction "VOUT_2") (pintype "passive"))
      (node (ref "U2") (pin "4") (pinfunction "VOUT_4") (pintype "passive"))
    )
    (net (code "66") (name "VCC_5V") (class "Default")
      (node (ref "C8") (pin "2") (pinfunction "2_2") (pintype "passive"))
      (node (ref "C9") (pin "2") (pinfunction "2_2") (pintype "passive"))
      (node (ref "J1") (pin "21") (pinfunction "21_21") (pintype "passive"))
      (node (ref "U2") (pin "3") (pinfunction "VIN_3") (pintype "passive"))
    )
    (net (code "67") (name "unconnected-(J2-Pad1)") (class "Default")
      (node (ref "J2") (pin "1") (pinfunction "1_1") (pintype "passive"))
    )
    (net (code "68") (name "unconnected-(J2-Pad21)") (class "Default")
      (node (ref "J2") (pin "21") (pinfunction "21_21") (pintype "passive"))
    )
    (net (code "69") (name "unconnected-(J2-Pad22)") (class "Default")
      (node (ref "J2") (pin "22") (pinfunction "22_22") (pintype "passive"))
    )
    (net (code "70") (name "unconnected-(SW1-Pad2)") (class "Default")
      (node (ref "SW1") (pin "2") (pinfunction "2_2") (pintype "passive+no_connect"))
    )
    (net (code "71") (name "unconnected-(SW1-Pad4)") (class "Default")
      (node (ref "SW1") (pin "4") (pinfunction "4_4") (pintype "passive+no_connect"))
    )
    (net (code "72") (name "unconnected-(SW2-Pad2)") (class "Default")
      (node (ref "SW2") (pin "2") (pinfunction "2_2") (pintype "passive+no_connect"))
    )
    (net (code "73") (name "unconnected-(SW2-Pad4)") (class "Default")
      (node (ref "SW2") (pin "4") (pinfunction "4_4") (pintype "passive+no_connect"))
    )
    (net (code "74") (name "unconnected-(U1-CTS-Pad23)") (class "Default")
      (node (ref "U1") (pin "23") (pinfunction "CTS_23") (pintype "passive+no_connect"))
    )
    (net (code "75") (name "unconnected-(U1-DCD-Pad1)") (class "Default")
      (node (ref "U1") (pin "1") (pinfunction "DCD_1") (pintype "passive+no_connect"))
    )
    (net (code "76") (name "unconnected-(U1-DSR-Pad27)") (class "Default")
      (node (ref "U1") (pin "27") (pinfunction "DSR_27") (pintype "passive+no_connect"))
    )
    (net (code "77") (name "unconnected-(U1-NC1-Pad10)") (class "Default")
      (node (ref "U1") (pin "10") (pinfunction "NC1_10") (pintype "passive+no_connect"))
    )
    (net (code "78") (name "unconnected-(U1-NC2-Pad13)") (class "Default")
      (node (ref "U1") (pin "13") (pinfunction "NC2_13") (pintype "passive+no_connect"))
    )
    (net (code "79") (name "unconnected-(U1-NC3-Pad14)") (class "Default")
      (node (ref "U1") (pin "14") (pinfunction "NC3_14") (pintype "passive+no_connect"))
    )
    (net (code "80") (name "unconnected-(U1-NC4-Pad15)") (class "Default")
      (node (ref "U1") (pin "15") (pinfunction "NC4_15") (pintype "passive+no_connect"))
    )
    (net (code "81") (name "unconnected-(U1-NC5-Pad16)") (class "Default")
      (node (ref "U1") (pin "16") (pinfunction "NC5_16") (pintype "passive+no_connect"))
    )
    (net (code "82") (name "unconnected-(U1-NC6-Pad17)") (class "Default")
      (node (ref "U1") (pin "17") (pinfunction "NC6_17") (pintype "passive+no_connect"))
    )
    (net (code "83") (name "unconnected-(U1-NC7-Pad18)") (class "Default")
      (node (ref "U1") (pin "18") (pinfunction "NC7_18") (pintype "passive+no_connect"))
    )
    (net (code "84") (name "unconnected-(U1-NC8-Pad19)") (class "Default")
      (node (ref "U1") (pin "19") (pinfunction "NC8_19") (pintype "passive+no_connect"))
    )
    (net (code "85") (name "unconnected-(U1-NC9-Pad20)") (class "Default")
      (node (ref "U1") (pin "20") (pinfunction "NC9_20") (pintype "passive+no_connect"))
    )
    (net (code "86") (name "unconnected-(U1-NC10-Pad21)") (class "Default")
      (node (ref "U1") (pin "21") (pinfunction "NC10_21") (pintype "passive+no_connect"))
    )
    (net (code "87") (name "unconnected-(U1-NC11-Pad22)") (class "Default")
      (node (ref "U1") (pin "22") (pinfunction "NC11_22") (pintype "passive+no_connect"))
    )
    (net (code "88") (name "unconnected-(U1-RI-Pad2)") (class "Default")
      (node (ref "U1") (pin "2") (pinfunction "RI_2") (pintype "passive+no_connect"))
    )
    (net (code "89") (name "unconnected-(U1-SUSPEND-Pad12)") (class "Default")
      (node (ref "U1") (pin "12") (pinfunction "SUSPEND_12") (pintype "passive+no_connect"))
    )
    (net (code "90") (name "unconnected-(USB1-SBU1-PadA8)") (class "Default")
      (node (ref "USB1") (pin "A8") (pinfunction "SBU1_A8") (pintype "passive+no_connect"))
    )
    (net (code "91") (name "unconnected-(USB1-SBU2-PadB8)") (class "Default")
      (node (ref "USB1") (pin "B8") (pinfunction "SBU2_B8") (pintype "passive+no_connect"))
    )
    (net (code "92") (name "unconnected-(USB2-SBU1-PadA8)") (class "Default")
      (node (ref "USB2") (pin "A8") (pinfunction "SBU1_A8") (pintype "passive+no_connect"))
    )
    (net (code "93") (name "unconnected-(USB2-SBU2-PadB8)") (class "Default")
      (node (ref "USB2") (pin "B8") (pinfunction "SBU2_B8") (pintype "passive+no_connect"))
    )
  )
)
